# IO.net
KiCad netlist of a schematic drawn in Altium Designer
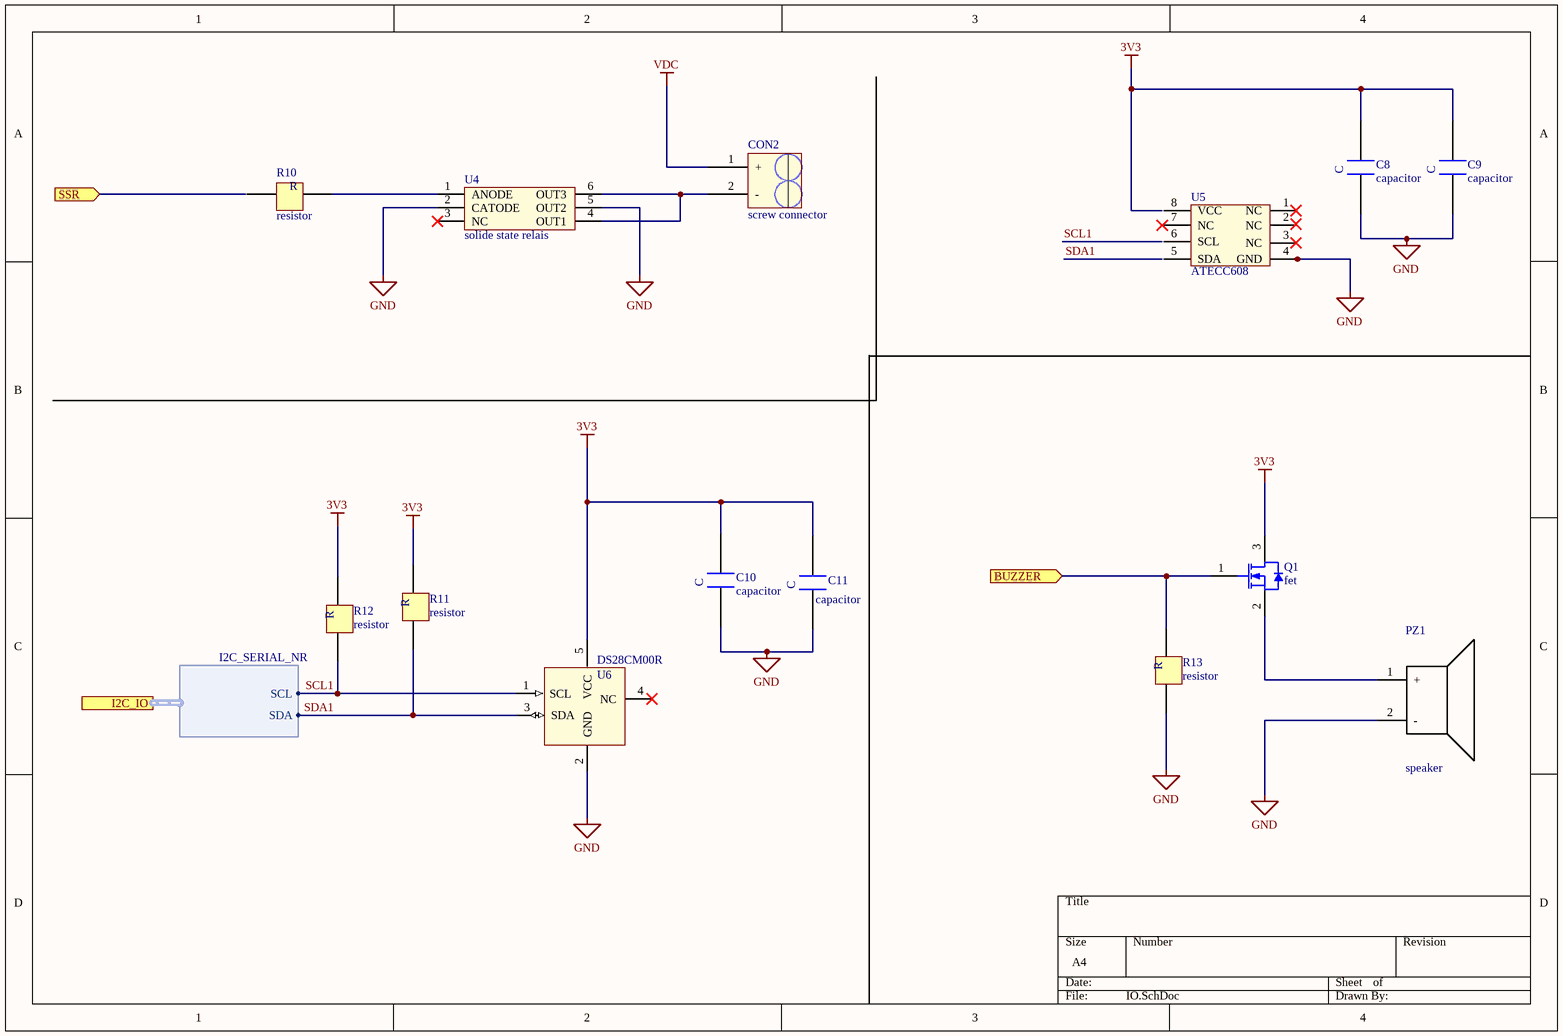
[diagram p0: IO.SchDoc]

(export (version "E")
  (design (tool "Eeschema 10.0.6"))
  (components
    (comp (ref "C8")
      (value "capacitor")
      (footprint "CAPC1005X04L")
      (libsource (lib "pasives") (part "capacitor"))
    )
    (comp (ref "C9")
      (value "capacitor")
      (footprint "CAPC1005X04L")
      (libsource (lib "pasives") (part "capacitor"))
    )
    (comp (ref "C10")
      (value "capacitor")
      (footprint "CAPC1005X04L")
      (libsource (lib "pasives") (part "capacitor"))
    )
    (comp (ref "C11")
      (value "capacitor")
      (footprint "CAPC1005X04L")
      (libsource (lib "pasives") (part "capacitor"))
    )
    (comp (ref "CON2")
      (value "screw connector")
      (footprint "SCREW connector 5mm pitch")
      (libsource (lib "conector's_and_TP") (part "screw connector"))
    )
    (comp (ref "PZ1") (value "speaker") (libsource (lib "pasives") (part "speaker")))
    (comp (ref "Q1") (value "fet") (libsource (lib "halfgelijders") (part "fet")))
    (comp (ref "R10") (value "resistor") (footprint "0603") (libsource (lib "") (part "resistor_1")))
    (comp (ref "R11")
      (value "resistor")
      (footprint "CAPC1005X04L")
      (libsource (lib "pasives") (part "resistor"))
    )
    (comp (ref "R12")
      (value "resistor")
      (footprint "CAPC1005X04L")
      (libsource (lib "pasives") (part "resistor"))
    )
    (comp (ref "R13")
      (value "resistor")
      (footprint "CAPC1005X04L")
      (libsource (lib "pasives") (part "resistor"))
    )
    (comp (ref "U4")
      (value "solide state relais")
      (libsource (lib "halfgelijders") (part "G3VM-61HR2(TR05)"))
    )
    (comp (ref "U5") (value "ATECC608") (libsource (lib "halfgelijders") (part "ATECC608")))
    (comp (ref "U6") (value "DS28CM00R") (libsource (lib "halfgelijders") (part "DS28CM00R")))
  )
  (nets
    (net (code "2") (name "/BUZZER") (class "Default")
      (node (ref "Q1") (pin "1") (pinfunction "1_1") (pintype "passive"))
      (node (ref "R13") (pin "1") (pinfunction "1_1") (pintype "passive"))
    )
    (net (code "3") (name "/SCL1") (class "Default")
      (node (ref "R12") (pin "2") (pinfunction "2_2") (pintype "passive"))
      (node (ref "U6") (pin "1") (pinfunction "SCL_1") (pintype "input"))
    )
    (net (code "4") (name "/SDA1") (class "Default")
      (node (ref "R11") (pin "2") (pinfunction "2_2") (pintype "passive"))
      (node (ref "U6") (pin "3") (pinfunction "SDA_3") (pintype "bidirectional"))
    )
    (net (code "7") (name "3V3") (class "Default")
      (node (ref "C10") (pin "1") (pinfunction "1_1") (pintype "passive"))
      (node (ref "C11") (pin "1") (pinfunction "1_1") (pintype "passive"))
      (node (ref "C8") (pin "1") (pinfunction "1_1") (pintype "passive"))
      (node (ref "C9") (pin "1") (pinfunction "1_1") (pintype "passive"))
      (node (ref "Q1") (pin "3") (pinfunction "3_3") (pintype "passive"))
      (node (ref "R11") (pin "1") (pinfunction "1_1") (pintype "passive"))
      (node (ref "R12") (pin "1") (pinfunction "1_1") (pintype "passive"))
      (node (ref "U6") (pin "5") (pinfunction "VCC_5") (pintype "passive"))
    )
    (net (code "8") (name "GND") (class "Default")
      (node (ref "C10") (pin "2") (pinfunction "2_2") (pintype "passive"))
      (node (ref "C11") (pin "2") (pinfunction "2_2") (pintype "passive"))
      (node (ref "C8") (pin "2") (pinfunction "2_2") (pintype "passive"))
      (node (ref "C9") (pin "2") (pinfunction "2_2") (pintype "passive"))
      (node (ref "PZ1") (pin "2") (pinfunction "-_2") (pintype "passive"))
      (node (ref "R13") (pin "2") (pinfunction "2_2") (pintype "passive"))
      (node (ref "U4") (pin "2") (pinfunction "CATODE_2") (pintype "passive"))
      (node (ref "U4") (pin "5") (pinfunction "OUT2_5") (pintype "passive"))
      (node (ref "U5") (pin "4") (pinfunction "GND_4") (pintype "power_in"))
      (node (ref "U6") (pin "2") (pinfunction "GND_2") (pintype "power_in"))
    )
    (net (code "9") (name "Net-(CON2--)") (class "Default")
      (node (ref "CON2") (pin "2") (pinfunction "-_2") (pintype "passive"))
      (node (ref "U4") (pin "4") (pinfunction "OUT1_4") (pintype "passive"))
      (node (ref "U4") (pin "6") (pinfunction "OUT3_6") (pintype "passive"))
    )
    (net (code "10") (name "Net-(PZ1-+)") (class "Default")
      (node (ref "PZ1") (pin "1") (pinfunction "+_1") (pintype "passive"))
      (node (ref "Q1") (pin "2") (pinfunction "2_2") (pintype "passive"))
    )
    (net (code "11") (name "Net-(U4-ANODE)") (class "Default")
      (node (ref "R10") (pin "1") (pinfunction "1_1") (pintype "passive"))
      (node (ref "U4") (pin "1") (pinfunction "ANODE_1") (pintype "passive"))
    )
    (net (code "12") (name "VDC") (class "Default")
      (node (ref "CON2") (pin "1") (pinfunction "+_1") (pintype "passive"))
    )
    (net (code "13") (name "unconnected-(R10-Pad2)") (class "Default")
      (node (ref "R10") (pin "2") (pinfunction "2_2") (pintype "passive"))
    )
    (net (code "14") (name "unconnected-(U4-NC-Pad3)") (class "Default")
      (node (ref "U4") (pin "3") (pinfunction "NC_3") (pintype "passive+no_connect"))
    )
    (net (code "15") (name "unconnected-(U5-NC-Pad1)") (class "Default")
      (node (ref "U5") (pin "1") (pinfunction "NC_1") (pintype "passive"))
    )
    (net (code "16") (name "unconnected-(U5-NC-Pad2)") (class "Default")
      (node (ref "U5") (pin "2") (pinfunction "NC_2") (pintype "passive"))
    )
    (net (code "17") (name "unconnected-(U5-NC-Pad3)") (class "Default")
      (node (ref "U5") (pin "3") (pinfunction "NC_3") (pintype "passive"))
    )
    (net (code "18") (name "unconnected-(U5-NC-Pad7)") (class "Default")
      (node (ref "U5") (pin "7") (pinfunction "NC_7") (pintype "passive"))
    )
    (net (code "19") (name "unconnected-(U5-SCL-Pad6)") (class "Default")
      (node (ref "U5") (pin "6") (pinfunction "SCL_6") (pintype "open_collector"))
    )
    (net (code "20") (name "unconnected-(U5-SDA-Pad5)") (class "Default")
      (node (ref "U5") (pin "5") (pinfunction "SDA_5") (pintype "open_collector"))
    )
    (net (code "21") (name "unconnected-(U5-VCC-Pad8)") (class "Default")
      (node (ref "U5") (pin "8") (pinfunction "VCC_8") (pintype "power_in"))
    )
    (net (code "22") (name "unconnected-(U6-NC-Pad4)") (class "Default")
      (node (ref "U6") (pin "4") (pinfunction "NC_4") (pintype "passive+no_connect"))
    )
  )
)
